# Mechaduino01.net
KiCad netlist of a schematic drawn in EAGLE
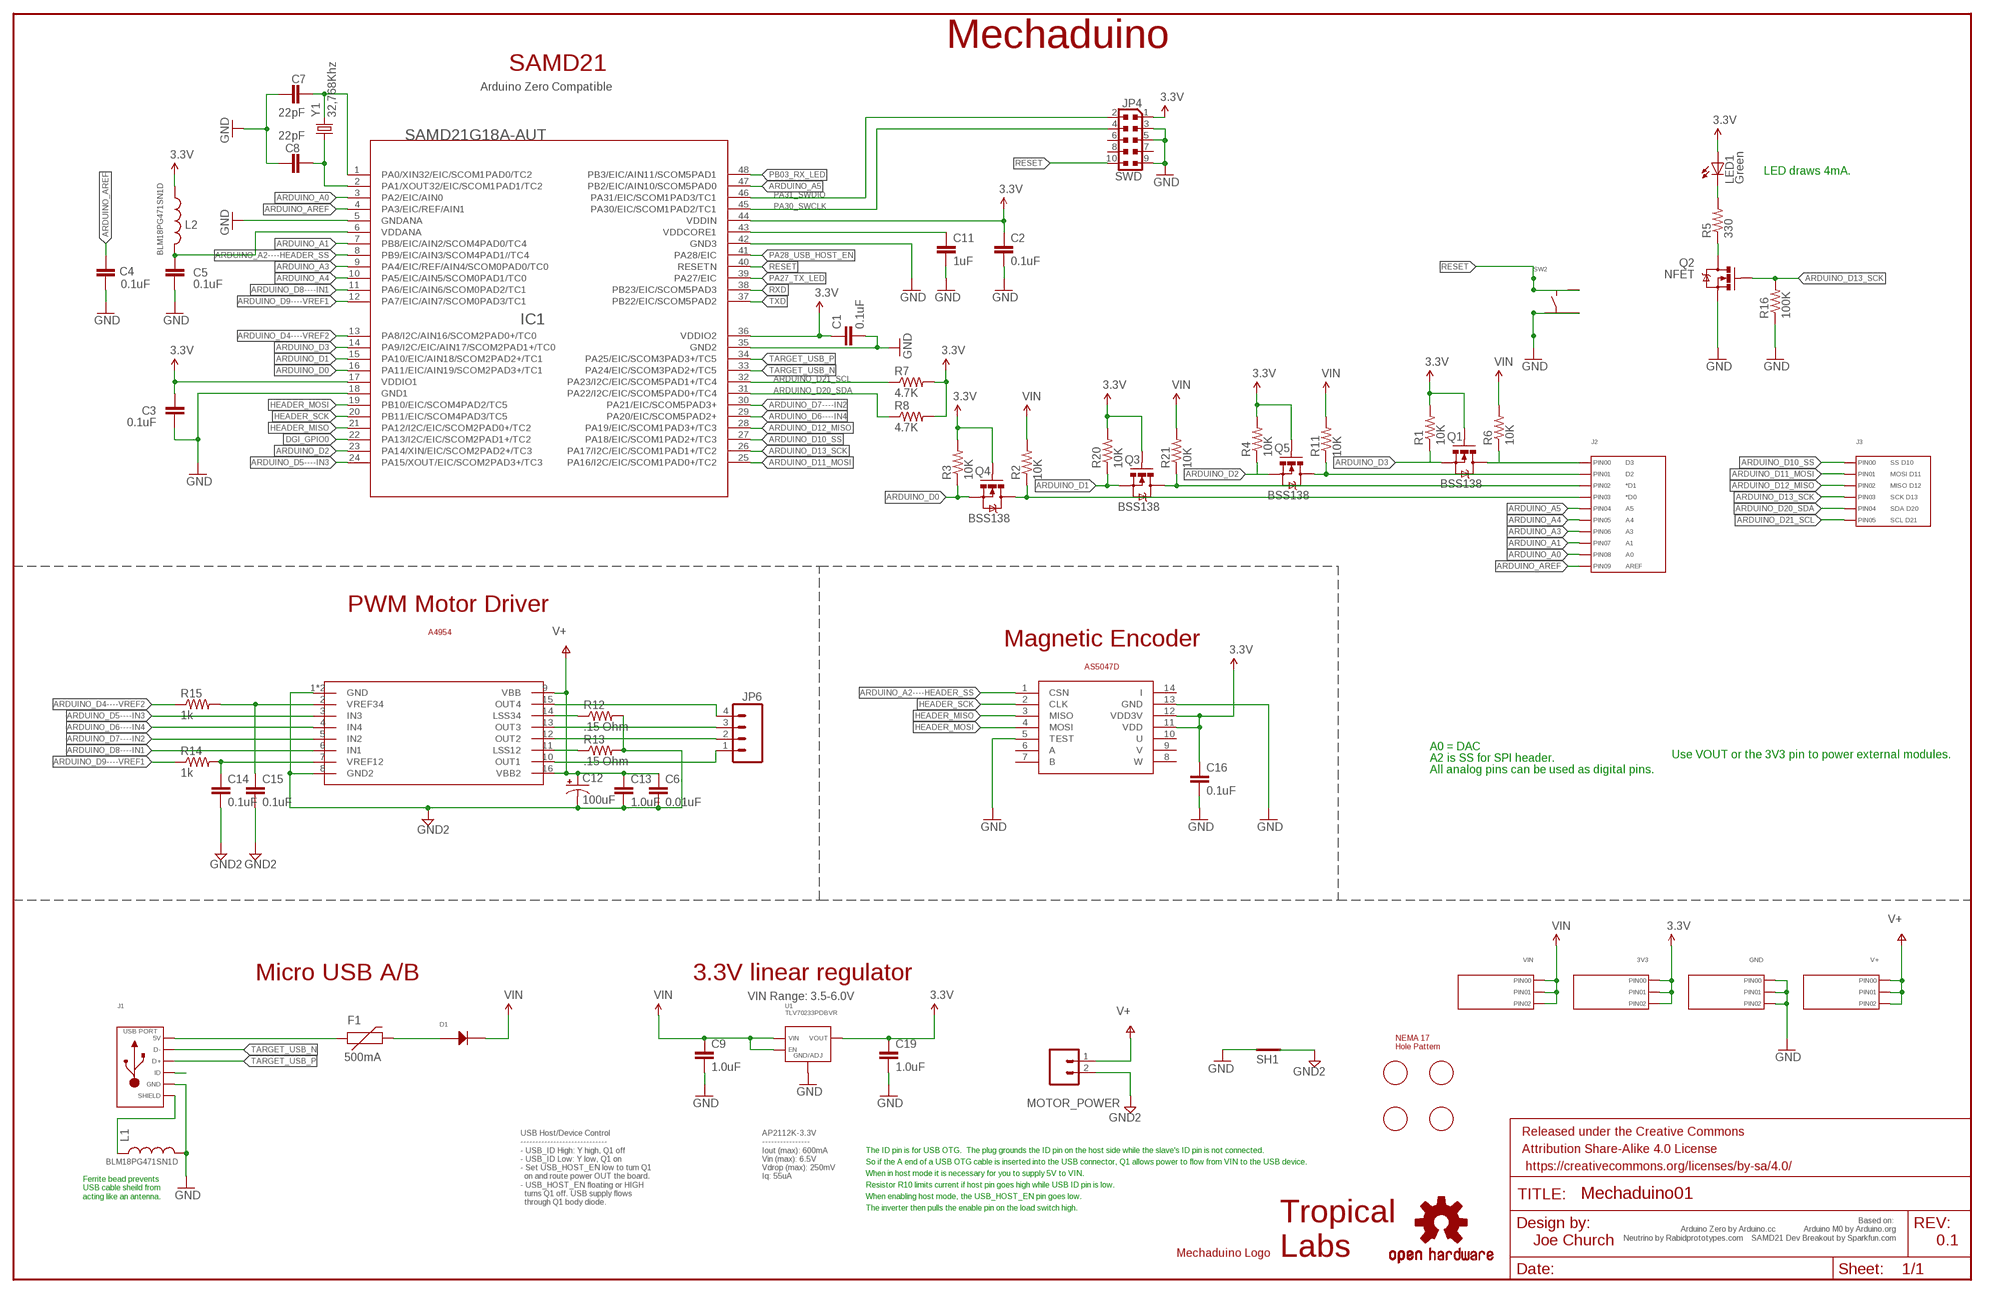
[diagram p0: schematic, sheet 1]

(export (version "E")
  (design (tool "Eeschema 10.0.6"))
  (components
    (comp (ref "3V3")
      (value "HEADER_01X03_PTH_2.54MM")
      (footprint "eagle-import:PTH_2.54MM_01X03")
      (libsource (lib "eagle-import") (part "HEADER_01X03_PTH_2.54MM"))
    )
    (comp (ref "C1")
      (value "0.1uF")
      (footprint "eagle-import:0402-CAP")
      (libsource (lib "eagle-import") (part "CAP0402"))
    )
    (comp (ref "C2")
      (value "0.1uF")
      (footprint "eagle-import:0402-CAP")
      (libsource (lib "eagle-import") (part "CAP0402"))
    )
    (comp (ref "C3")
      (value "0.1uF")
      (footprint "eagle-import:0402-CAP")
      (libsource (lib "eagle-import") (part "CAP0402"))
    )
    (comp (ref "C4")
      (value "0.1uF")
      (footprint "eagle-import:0402-CAP")
      (libsource (lib "eagle-import") (part "CAP0402"))
    )
    (comp (ref "C5")
      (value "0.1uF")
      (footprint "eagle-import:0402-CAP")
      (libsource (lib "eagle-import") (part "CAP0402"))
    )
    (comp (ref "C6")
      (value "0.01uF")
      (footprint "eagle-import:0402-CAP")
      (libsource (lib "eagle-import") (part "CAP0402"))
    )
    (comp (ref "C7")
      (value "22pF")
      (footprint "eagle-import:0402-CAP")
      (libsource (lib "eagle-import") (part "CAP0402"))
    )
    (comp (ref "C8")
      (value "22pF")
      (footprint "eagle-import:0402-CAP")
      (libsource (lib "eagle-import") (part "CAP0402"))
    )
    (comp (ref "C9")
      (value "1.0uF")
      (footprint "eagle-import:0402-CAP")
      (libsource (lib "eagle-import") (part "CAP0402"))
    )
    (comp (ref "C11")
      (value "1uF")
      (footprint "eagle-import:0402-CAP")
      (libsource (lib "eagle-import") (part "CAP0402"))
    )
    (comp (ref "C12")
      (value "100uF")
      (footprint "eagle-import:PANASONIC_D")
      (libsource (lib "eagle-import") (part "CAP_POLD"))
    )
    (comp (ref "C13")
      (value "1.0uF")
      (footprint "eagle-import:0603-CAP")
      (libsource (lib "eagle-import") (part "CAP0603"))
    )
    (comp (ref "C14")
      (value "0.1uF")
      (footprint "eagle-import:0402-CAP")
      (libsource (lib "eagle-import") (part "CAP0402"))
    )
    (comp (ref "C15")
      (value "0.1uF")
      (footprint "eagle-import:0402-CAP")
      (libsource (lib "eagle-import") (part "CAP0402"))
    )
    (comp (ref "C16")
      (value "0.1uF")
      (footprint "eagle-import:0402-CAP")
      (libsource (lib "eagle-import") (part "CAP0402"))
    )
    (comp (ref "C19")
      (value "1.0uF")
      (footprint "eagle-import:0402-CAP")
      (libsource (lib "eagle-import") (part "CAP0402"))
    )
    (comp (ref "D1")
      (value "DIODE_SOD-123")
      (footprint "eagle-import:SOD-123")
      (libsource (lib "eagle-import") (part "DIODE_SOD-123"))
    )
    (comp (ref "F1")
      (value "500mA")
      (footprint "eagle-import:PTC-1206")
      (libsource (lib "eagle-import") (part "PTCSMD"))
    )
    (comp (ref "FRAME1")
      (value "FRAME-LEDGER")
      (footprint "eagle-import:CREATIVE_COMMONS")
      (libsource (lib "eagle-import") (part "FRAME-LEDGER"))
    )
    (comp (ref "GND")
      (value "HEADER_01X03_PTH_2.54MM")
      (footprint "eagle-import:PTH_2.54MM_01X03")
      (libsource (lib "eagle-import") (part "HEADER_01X03_PTH_2.54MM"))
    )
    (comp (ref "IC1")
      (value "SAMD21G18A-AUT")
      (footprint "eagle-import:INTEGRATEDCIRCUITS_TQFP48-7X7")
      (libsource (lib "eagle-import") (part "INTEGRATEDCIRCUITS_1792_SAMD21G18A-AUT"))
    )
    (comp (ref "J1")
      (value "USB_MICRO_RIGHT")
      (footprint "eagle-import:MICROUSB-RIGHT")
      (libsource (lib "eagle-import") (part "USB_MICRO_RIGHT"))
    )
    (comp (ref "J2")
      (value "HEADER_01X10_PTH_2.54MM")
      (footprint "eagle-import:PTH_2.54MM_01X10")
      (fields
        (field (name "LABEL00") "D3")
        (field (name "LABEL01") "D2")
        (field (name "LABEL02") "*D1")
        (field (name "LABEL03") "*D0")
        (field (name "LABEL04") "A5")
        (field (name "LABEL05") "A4")
        (field (name "LABEL06") "A3")
        (field (name "LABEL07") "A1")
        (field (name "LABEL08") "A0")
        (field (name "LABEL09") "AREF")
      )
      (libsource (lib "eagle-import") (part "HEADER_01X10_PTH_2.54MM"))
    )
    (comp (ref "J3")
      (value "HEADER_01X06_PTH_2.54MM")
      (footprint "eagle-import:PTH_2.54MM_01X06")
      (fields
        (field (name "LABEL00") "SS D10")
        (field (name "LABEL01") "MOSI D11")
        (field (name "LABEL02") "MISO D12")
        (field (name "LABEL03") "SCK D13")
        (field (name "LABEL04") "SDA D20")
        (field (name "LABEL05") "SCL D21")
      )
      (libsource (lib "eagle-import") (part "HEADER_01X06_PTH_2.54MM"))
    )
    (comp (ref "JP4")
      (value "SWD")
      (footprint "eagle-import:CONNETTORI_PINHEAD-2X5-P127")
      (libsource (lib "eagle-import") (part "CONNETTORI_0171_PH127-205DF055G00A"))
    )
    (comp (ref "JP6")
      (value "M04PTH")
      (footprint "eagle-import:1X04")
      (libsource (lib "eagle-import") (part "M04PTH"))
    )
    (comp (ref "L1")
      (value "BLM18PG471SN1D")
      (footprint "eagle-import:0603-TDK")
      (libsource (lib "eagle-import") (part "INDUCTOR0603-TDK"))
    )
    (comp (ref "L2")
      (value "BLM18PG471SN1D")
      (footprint "eagle-import:0603-TDK")
      (libsource (lib "eagle-import") (part "INDUCTOR0603-TDK"))
    )
    (comp (ref "LED1")
      (value "Green")
      (footprint "eagle-import:CHIPLED_0805")
      (fields (field (name "PART_NUMBER") "KPT-2012YC"))
      (libsource (lib "eagle-import") (part "0044_KPT-2012YC"))
    )
    (comp (ref "LOGO4")
      (value "OSHW-LOGOL-COPPER")
      (footprint "eagle-import:OSHW-LOGO-L_COPPER")
      (libsource (lib "eagle-import") (part "OSHW-LOGOL-COPPER"))
    )
    (comp (ref "MOTOR_POWER")
      (value "M025MM")
      (footprint "eagle-import:SCREWTERMINAL-5MM-2")
      (libsource (lib "eagle-import") (part "M025MM"))
    )
    (comp (ref "Q1")
      (value "BSS138")
      (footprint "eagle-import:SOT23-3")
      (libsource (lib "eagle-import") (part "MOSFET-NCHANNELSMD"))
    )
    (comp (ref "Q2")
      (value "NFET")
      (footprint "eagle-import:SOT323")
      (libsource (lib "eagle-import") (part "MOSFET-NCHANNEL2N7002PW"))
    )
    (comp (ref "Q3")
      (value "BSS138")
      (footprint "eagle-import:SOT23-3")
      (libsource (lib "eagle-import") (part "MOSFET-NCHANNELSMD"))
    )
    (comp (ref "Q4")
      (value "BSS138")
      (footprint "eagle-import:SOT23-3")
      (libsource (lib "eagle-import") (part "MOSFET-NCHANNELSMD"))
    )
    (comp (ref "Q5")
      (value "BSS138")
      (footprint "eagle-import:SOT23-3")
      (libsource (lib "eagle-import") (part "MOSFET-NCHANNELSMD"))
    )
    (comp (ref "R1")
      (value "10K")
      (footprint "eagle-import:R0402-VISHAY")
      (libsource (lib "eagle-import") (part "R-US_R0402-VISHAY"))
    )
    (comp (ref "R2")
      (value "10K")
      (footprint "eagle-import:R0402-VISHAY")
      (libsource (lib "eagle-import") (part "R-US_R0402-VISHAY"))
    )
    (comp (ref "R3")
      (value "10K")
      (footprint "eagle-import:R0402-VISHAY")
      (libsource (lib "eagle-import") (part "R-US_R0402-VISHAY"))
    )
    (comp (ref "R4")
      (value "10K")
      (footprint "eagle-import:R0402-VISHAY")
      (libsource (lib "eagle-import") (part "R-US_R0402-VISHAY"))
    )
    (comp (ref "R5")
      (value "330")
      (footprint "eagle-import:R0402-VISHAY")
      (libsource (lib "eagle-import") (part "R-US_R0402-VISHAY"))
    )
    (comp (ref "R6")
      (value "10K")
      (footprint "eagle-import:R0402-VISHAY")
      (libsource (lib "eagle-import") (part "R-US_R0402-VISHAY"))
    )
    (comp (ref "R7")
      (value "4.7K")
      (footprint "eagle-import:R0402-VISHAY")
      (libsource (lib "eagle-import") (part "R-US_R0402-VISHAY"))
    )
    (comp (ref "R8")
      (value "4.7K")
      (footprint "eagle-import:R0402-VISHAY")
      (libsource (lib "eagle-import") (part "R-US_R0402-VISHAY"))
    )
    (comp (ref "R11")
      (value "10K")
      (footprint "eagle-import:R0402-VISHAY")
      (libsource (lib "eagle-import") (part "R-US_R0402-VISHAY"))
    )
    (comp (ref "R12")
      (value ".15 Ohm")
      (footprint "eagle-import:R1206")
      (libsource (lib "eagle-import") (part "R-US_R1206"))
    )
    (comp (ref "R13")
      (value ".15 Ohm")
      (footprint "eagle-import:R1206")
      (libsource (lib "eagle-import") (part "R-US_R1206"))
    )
    (comp (ref "R14")
      (value "1k")
      (footprint "eagle-import:R0402-VISHAY")
      (libsource (lib "eagle-import") (part "R-US_R0402-VISHAY"))
    )
    (comp (ref "R15")
      (value "1k")
      (footprint "eagle-import:R0402-VISHAY")
      (libsource (lib "eagle-import") (part "R-US_R0402-VISHAY"))
    )
    (comp (ref "R16")
      (value "100K")
      (footprint "eagle-import:R0402-VISHAY")
      (libsource (lib "eagle-import") (part "R-US_R0402-VISHAY"))
    )
    (comp (ref "R20")
      (value "10K")
      (footprint "eagle-import:R0402-VISHAY")
      (libsource (lib "eagle-import") (part "R-US_R0402-VISHAY"))
    )
    (comp (ref "R21")
      (value "10K")
      (footprint "eagle-import:R0402-VISHAY")
      (libsource (lib "eagle-import") (part "R-US_R0402-VISHAY"))
    )
    (comp (ref "SH1")
      (value "SHORT-HA5")
      (footprint "eagle-import:SHORT_ALL-50")
      (libsource (lib "eagle-import") (part "SHORT-HA5"))
    )
    (comp (ref "SW2")
      (value "TACT_4.2MM")
      (footprint "eagle-import:TACT4.2MM")
      (libsource (lib "eagle-import") (part "TACT_4.2MM"))
    )
    (comp (ref "U$1")
      (value "AVAGO_DRIVERTHERM")
      (footprint "eagle-import:TSSOP16_THERM")
      (libsource (lib "eagle-import") (part "AVAGO_DRIVERTHERM"))
    )
    (comp (ref "U$2")
      (value "NEMA17_HOLE_PATTERNNEW")
      (footprint "eagle-import:NEMA17_HOLE_PATTERN_2")
      (libsource (lib "eagle-import") (part "NEMA17_HOLE_PATTERNNEW"))
    )
    (comp (ref "U$3")
      (value "TROPICAL_LABS_LOGO_1LOGO3")
      (footprint "eagle-import:LOGO3")
      (libsource (lib "eagle-import") (part "TROPICAL_LABS_LOGO_1LOGO3"))
    )
    (comp (ref "U$4")
      (value "AS5047D")
      (footprint "eagle-import:TSSOP14")
      (libsource (lib "eagle-import") (part "AS5047D"))
    )
    (comp (ref "U$5")
      (value "MECHADUINO_LOGO")
      (footprint "eagle-import:MECHADUINO_LOGO")
      (libsource (lib "eagle-import") (part "MECHADUINO_LOGO"))
    )
    (comp (ref "U1")
      (value "TLV70233PDBVR")
      (footprint "eagle-import:SOT-23-5")
      (libsource (lib "eagle-import") (part "TLV70233PDBVR"))
    )
    (comp (ref "V+")
      (value "HEADER_01X03_PTH_2.54MM")
      (footprint "eagle-import:PTH_2.54MM_01X03")
      (libsource (lib "eagle-import") (part "HEADER_01X03_PTH_2.54MM"))
    )
    (comp (ref "VIN")
      (value "HEADER_01X03_PTH_2.54MM")
      (footprint "eagle-import:PTH_2.54MM_01X03")
      (libsource (lib "eagle-import") (part "HEADER_01X03_PTH_2.54MM"))
    )
    (comp (ref "Y1")
      (value "32,768Khz")
      (footprint "eagle-import:CRYSTAL-SMD-2.0X1.2")
      (libsource (lib "eagle-import") (part "CRYSTAL2012"))
    )
  )
  (nets
    (net (code "1") (name "/PA30_SWCLK") (class "Default")
      (node (ref "IC1") (pin "45") (pinfunction "PA30/EIC/SCOM1PAD2/TC1_45") (pintype "bidirectional"))
      (node (ref "JP4") (pin "4") (pinfunction "4_4") (pintype "passive"))
    )
    (net (code "2") (name "/PA31_SWDIO") (class "Default")
      (node (ref "IC1") (pin "46") (pinfunction "PA31/EIC/SCOM1PAD3/TC1_46") (pintype "bidirectional"))
      (node (ref "JP4") (pin "2") (pinfunction "2_2") (pintype "passive"))
    )
    (net (code "3") (name "3.3V") (class "Default")
      (node (ref "3V3") (pin "P$1") (pinfunction "PIN0_P$1") (pintype "bidirectional"))
      (node (ref "3V3") (pin "P$2") (pinfunction "PIN1_P$2") (pintype "bidirectional"))
      (node (ref "3V3") (pin "P$3") (pinfunction "PIN2_P$3") (pintype "bidirectional"))
      (node (ref "C1") (pin "1") (pinfunction "1_1") (pintype "passive"))
      (node (ref "C16") (pin "1") (pinfunction "1_1") (pintype "passive"))
      (node (ref "C19") (pin "1") (pinfunction "1_1") (pintype "passive"))
      (node (ref "C2") (pin "1") (pinfunction "1_1") (pintype "passive"))
      (node (ref "C3") (pin "2") (pinfunction "2_2") (pintype "passive"))
      (node (ref "IC1") (pin "17") (pinfunction "VDDIO1_17") (pintype "power_in"))
      (node (ref "IC1") (pin "36") (pinfunction "VDDIO2_36") (pintype "power_in"))
      (node (ref "IC1") (pin "44") (pinfunction "VDDIN_44") (pintype "power_in"))
      (node (ref "JP4") (pin "1") (pinfunction "1_1") (pintype "passive"))
      (node (ref "L2") (pin "1") (pinfunction "1_1") (pintype "passive"))
      (node (ref "LED1") (pin "A") (pinfunction "A_A") (pintype "passive"))
      (node (ref "Q1") (pin "1") (pinfunction "G_1") (pintype "passive"))
      (node (ref "Q3") (pin "1") (pinfunction "G_1") (pintype "passive"))
      (node (ref "Q4") (pin "1") (pinfunction "G_1") (pintype "passive"))
      (node (ref "Q5") (pin "1") (pinfunction "G_1") (pintype "passive"))
      (node (ref "R1") (pin "2") (pinfunction "2_2") (pintype "passive"))
      (node (ref "R20") (pin "2") (pinfunction "2_2") (pintype "passive"))
      (node (ref "R3") (pin "2") (pinfunction "2_2") (pintype "passive"))
      (node (ref "R4") (pin "2") (pinfunction "2_2") (pintype "passive"))
      (node (ref "R7") (pin "2") (pinfunction "2_2") (pintype "passive"))
      (node (ref "R8") (pin "2") (pinfunction "2_2") (pintype "passive"))
      (node (ref "U$4") (pin "11") (pinfunction "VDD_11") (pintype "bidirectional"))
      (node (ref "U$4") (pin "12") (pinfunction "VDD3V_12") (pintype "bidirectional"))
      (node (ref "U1") (pin "P$5") (pinfunction "VOUT_P$5") (pintype "bidirectional"))
    )
    (net (code "4") (name "ARDUINO_A0") (class "Default")
      (node (ref "IC1") (pin "3") (pinfunction "PA2/EIC/AIN0_3") (pintype "bidirectional"))
      (node (ref "J2") (pin "P$9") (pinfunction "PIN8_P$9") (pintype "bidirectional"))
    )
    (net (code "5") (name "ARDUINO_A1") (class "Default")
      (node (ref "IC1") (pin "7") (pinfunction "PB8/EIC/AIN2/SCOM4PAD0/TC4_7") (pintype "bidirectional"))
      (node (ref "J2") (pin "P$8") (pinfunction "PIN7_P$8") (pintype "bidirectional"))
    )
    (net (code "6") (name "ARDUINO_A2----HEADER_SS") (class "Default")
      (node (ref "IC1") (pin "8") (pinfunction "PB9/EIC/AIN3/SCOM4PAD1//TC4_8") (pintype "bidirectional"))
      (node (ref "U$4") (pin "1") (pinfunction "CSN_1") (pintype "bidirectional"))
    )
    (net (code "7") (name "ARDUINO_A3") (class "Default")
      (node (ref "IC1") (pin "9") (pinfunction "PA4/EIC/REF/AIN4/SCOM0PAD0/TC0_9") (pintype "bidirectional"))
      (node (ref "J2") (pin "P$7") (pinfunction "PIN6_P$7") (pintype "bidirectional"))
    )
    (net (code "8") (name "ARDUINO_A4") (class "Default")
      (node (ref "IC1") (pin "10") (pinfunction "PA5/EIC/AIN5/SCOM0PAD1/TC0_10") (pintype "bidirectional"))
      (node (ref "J2") (pin "P$6") (pinfunction "PIN5_P$6") (pintype "bidirectional"))
    )
    (net (code "9") (name "ARDUINO_A5") (class "Default")
      (node (ref "IC1") (pin "47") (pinfunction "PB2/EIC/AIN10/SCOM5PAD0_47") (pintype "bidirectional"))
      (node (ref "J2") (pin "P$5") (pinfunction "PIN4_P$5") (pintype "bidirectional"))
    )
    (net (code "10") (name "ARDUINO_AREF") (class "Default")
      (node (ref "C4") (pin "1") (pinfunction "1_1") (pintype "passive"))
      (node (ref "IC1") (pin "4") (pinfunction "PA3/EIC/REF/AIN1_4") (pintype "bidirectional"))
      (node (ref "J2") (pin "P$10") (pinfunction "PIN9_P$10") (pintype "bidirectional"))
    )
    (net (code "11") (name "ARDUINO_D0") (class "Default")
      (node (ref "IC1") (pin "16") (pinfunction "PA11/EIC/AIN19/SCOM2PAD3+/TC1_16") (pintype "bidirectional"))
      (node (ref "Q4") (pin "2") (pinfunction "S_2") (pintype "passive"))
      (node (ref "R3") (pin "1") (pinfunction "1_1") (pintype "passive"))
    )
    (net (code "12") (name "ARDUINO_D1") (class "Default")
      (node (ref "IC1") (pin "15") (pinfunction "PA10/EIC/AIN18/SCOM2PAD2+/TC1_15") (pintype "bidirectional"))
      (node (ref "Q3") (pin "2") (pinfunction "S_2") (pintype "passive"))
      (node (ref "R20") (pin "1") (pinfunction "1_1") (pintype "passive"))
    )
    (net (code "13") (name "ARDUINO_D2") (class "Default")
      (node (ref "IC1") (pin "23") (pinfunction "PA14/XIN/EIC/SCOM2PAD2+/TC3_23") (pintype "bidirectional"))
      (node (ref "Q5") (pin "2") (pinfunction "S_2") (pintype "passive"))
      (node (ref "R4") (pin "1") (pinfunction "1_1") (pintype "passive"))
    )
    (net (code "14") (name "ARDUINO_D3") (class "Default")
      (node (ref "IC1") (pin "14") (pinfunction "PA9/I2C/EIC/AIN17/SCOM2PAD1+/TC0_14") (pintype "bidirectional"))
      (node (ref "Q1") (pin "2") (pinfunction "S_2") (pintype "passive"))
      (node (ref "R1") (pin "1") (pinfunction "1_1") (pintype "passive"))
    )
    (net (code "15") (name "ARDUINO_D4----VREF2") (class "Default")
      (node (ref "IC1") (pin "13") (pinfunction "PA8/I2C/AIN16/SCOM2PAD0+/TC0_13") (pintype "bidirectional"))
      (node (ref "R15") (pin "1") (pinfunction "1_1") (pintype "passive"))
    )
    (net (code "16") (name "ARDUINO_D5----IN3") (class "Default")
      (node (ref "IC1") (pin "24") (pinfunction "PA15/XOUT/EIC/SCOM2PAD3+/TC3_24") (pintype "bidirectional"))
      (node (ref "U$1") (pin "3") (pinfunction "IN3_3") (pintype "bidirectional"))
    )
    (net (code "17") (name "ARDUINO_D6----IN4") (class "Default")
      (node (ref "IC1") (pin "29") (pinfunction "PA20/EIC/SCOM5PAD2+_29") (pintype "bidirectional"))
      (node (ref "U$1") (pin "4") (pinfunction "IN4_4") (pintype "bidirectional"))
    )
    (net (code "18") (name "ARDUINO_D7----IN2") (class "Default")
      (node (ref "IC1") (pin "30") (pinfunction "PA21/EIC/SCOM5PAD3+_30") (pintype "bidirectional"))
      (node (ref "U$1") (pin "5") (pinfunction "IN2_5") (pintype "bidirectional"))
    )
    (net (code "19") (name "ARDUINO_D8----IN1") (class "Default")
      (node (ref "IC1") (pin "11") (pinfunction "PA6/EIC/AIN6/SCOM0PAD2/TC1_11") (pintype "bidirectional"))
      (node (ref "U$1") (pin "6") (pinfunction "IN1_6") (pintype "bidirectional"))
    )
    (net (code "20") (name "ARDUINO_D9----VREF1") (class "Default")
      (node (ref "IC1") (pin "12") (pinfunction "PA7/EIC/AIN7/SCOM0PAD3/TC1_12") (pintype "bidirectional"))
      (node (ref "R14") (pin "1") (pinfunction "1_1") (pintype "passive"))
    )
    (net (code "21") (name "ARDUINO_D10_SS") (class "Default")
      (node (ref "IC1") (pin "27") (pinfunction "PA18/EIC/SCOM1PAD2+/TC3_27") (pintype "bidirectional"))
      (node (ref "J3") (pin "P$1") (pinfunction "PIN0_P$1") (pintype "bidirectional"))
    )
    (net (code "22") (name "ARDUINO_D11_MOSI") (class "Default")
      (node (ref "IC1") (pin "25") (pinfunction "PA16/I2C/EIC/SCOM1PAD0+/TC2_25") (pintype "bidirectional"))
      (node (ref "J3") (pin "P$2") (pinfunction "PIN1_P$2") (pintype "bidirectional"))
    )
    (net (code "23") (name "ARDUINO_D12_MISO") (class "Default")
      (node (ref "IC1") (pin "28") (pinfunction "PA19/EIC/SCOM1PAD3+/TC3_28") (pintype "bidirectional"))
      (node (ref "J3") (pin "P$3") (pinfunction "PIN2_P$3") (pintype "bidirectional"))
    )
    (net (code "24") (name "ARDUINO_D13_SCK") (class "Default")
      (node (ref "IC1") (pin "26") (pinfunction "PA17/I2C/EIC/SCOM1PAD1+/TC2_26") (pintype "bidirectional"))
      (node (ref "J3") (pin "P$4") (pinfunction "PIN3_P$4") (pintype "bidirectional"))
      (node (ref "Q2") (pin "1") (pinfunction "G_1") (pintype "passive"))
      (node (ref "R16") (pin "2") (pinfunction "2_2") (pintype "passive"))
    )
    (net (code "25") (name "ARDUINO_D20_SDA") (class "Default")
      (node (ref "IC1") (pin "31") (pinfunction "PA22/I2C/EIC/SCOM5PAD0+/TC4_31") (pintype "bidirectional"))
      (node (ref "J3") (pin "P$5") (pinfunction "PIN4_P$5") (pintype "bidirectional"))
      (node (ref "R8") (pin "1") (pinfunction "1_1") (pintype "passive"))
    )
    (net (code "26") (name "ARDUINO_D21_SCL") (class "Default")
      (node (ref "IC1") (pin "32") (pinfunction "PA23/I2C/EIC/SCOM5PAD1+/TC4_32") (pintype "bidirectional"))
      (node (ref "J3") (pin "P$6") (pinfunction "PIN5_P$6") (pintype "bidirectional"))
      (node (ref "R7") (pin "1") (pinfunction "1_1") (pintype "passive"))
    )
    (net (code "27") (name "DGI_GPIO0") (class "Default")
      (node (ref "IC1") (pin "22") (pinfunction "PA13/I2C/EIC/SCOM2PAD1+/TC2_22") (pintype "bidirectional"))
    )
    (net (code "28") (name "GND") (class "Default")
      (node (ref "C1") (pin "2") (pinfunction "2_2") (pintype "passive"))
      (node (ref "C11") (pin "2") (pinfunction "2_2") (pintype "passive"))
      (node (ref "C16") (pin "2") (pinfunction "2_2") (pintype "passive"))
      (node (ref "C19") (pin "2") (pinfunction "2_2") (pintype "passive"))
      (node (ref "C2") (pin "2") (pinfunction "2_2") (pintype "passive"))
      (node (ref "C3") (pin "1") (pinfunction "1_1") (pintype "passive"))
      (node (ref "C4") (pin "2") (pinfunction "2_2") (pintype "passive"))
      (node (ref "C5") (pin "2") (pinfunction "2_2") (pintype "passive"))
      (node (ref "C7") (pin "1") (pinfunction "1_1") (pintype "passive"))
      (node (ref "C8") (pin "1") (pinfunction "1_1") (pintype "passive"))
      (node (ref "C9") (pin "2") (pinfunction "2_2") (pintype "passive"))
      (node (ref "GND") (pin "P$1") (pinfunction "PIN0_P$1") (pintype "bidirectional"))
      (node (ref "GND") (pin "P$2") (pinfunction "PIN1_P$2") (pintype "bidirectional"))
      (node (ref "GND") (pin "P$3") (pinfunction "PIN2_P$3") (pintype "bidirectional"))
      (node (ref "IC1") (pin "18") (pinfunction "GND1_18") (pintype "power_in"))
      (node (ref "IC1") (pin "35") (pinfunction "GND2_35") (pintype "power_in"))
      (node (ref "IC1") (pin "42") (pinfunction "GND3_42") (pintype "power_in"))
      (node (ref "IC1") (pin "5") (pinfunction "GNDANA_5") (pintype "power_in"))
      (node (ref "J1") (pin "5") (pinfunction "GND_5") (pintype "power_in"))
      (node (ref "JP4") (pin "3") (pinfunction "3_3") (pintype "passive"))
      (node (ref "JP4") (pin "5") (pinfunction "5_5") (pintype "passive"))
      (node (ref "JP4") (pin "9") (pinfunction "9_9") (pintype "passive"))
      (node (ref "L1") (pin "2") (pinfunction "2_2") (pintype "passive"))
      (node (ref "Q2") (pin "2") (pinfunction "S_2") (pintype "passive"))
      (node (ref "R16") (pin "1") (pinfunction "1_1") (pintype "passive"))
      (node (ref "SH1") (pin "2") (pinfunction "P$2_2") (pintype "bidirectional"))
      (node (ref "SW2") (pin "P$3") (pinfunction "P$3_P$3") (pintype "bidirectional"))
      (node (ref "SW2") (pin "P$4") (pinfunction "P$4_P$4") (pintype "bidirectional"))
      (node (ref "U$4") (pin "13") (pinfunction "GND_13") (pintype "bidirectional"))
      (node (ref "U$4") (pin "5") (pinfunction "TEST_5") (pintype "bidirectional"))
      (node (ref "U1") (pin "P$2") (pinfunction "GND/ADJ_P$2") (pintype "bidirectional"))
    )
    (net (code "29") (name "GND2") (class "Default")
      (node (ref "C12") (pin "-") (pinfunction "-_-") (pintype "passive"))
      (node (ref "C13") (pin "2") (pinfunction "2_2") (pintype "passive"))
      (node (ref "C14") (pin "2") (pinfunction "2_2") (pintype "passive"))
      (node (ref "C15") (pin "2") (pinfunction "2_2") (pintype "passive"))
      (node (ref "C6") (pin "2") (pinfunction "2_2") (pintype "passive"))
      (node (ref "MOTOR_POWER") (pin "2") (pinfunction "2_2") (pintype "passive"))
      (node (ref "R12") (pin "2") (pinfunction "2_2") (pintype "passive"))
      (node (ref "R13") (pin "2") (pinfunction "2_2") (pintype "passive"))
      (node (ref "SH1") (pin "1") (pinfunction "P$1_1") (pintype "bidirectional"))
      (node (ref "U$1") (pin "1") (pinfunction "GND_1") (pintype "bidirectional"))
      (node (ref "U$1") (pin "8") (pinfunction "GND2_8") (pintype "bidirectional"))
      (node (ref "U$1") (pin "P$1") (pinfunction "GND_P$1") (pintype "bidirectional"))
    )
    (net (code "30") (name "HEADER_MISO") (class "Default")
      (node (ref "IC1") (pin "21") (pinfunction "PA12/I2C/EIC/SCOM2PAD0+/TC2_21") (pintype "bidirectional"))
      (node (ref "U$4") (pin "3") (pinfunction "MISO_3") (pintype "bidirectional"))
    )
    (net (code "31") (name "HEADER_MOSI") (class "Default")
      (node (ref "IC1") (pin "19") (pinfunction "PB10/EIC/SCOM4PAD2/TC5_19") (pintype "bidirectional"))
      (node (ref "U$4") (pin "4") (pinfunction "MOSI_4") (pintype "bidirectional"))
    )
    (net (code "32") (name "HEADER_SCK") (class "Default")
      (node (ref "IC1") (pin "20") (pinfunction "PB11/EIC/SCOM4PAD3/TC5_20") (pintype "bidirectional"))
      (node (ref "U$4") (pin "2") (pinfunction "CLK_2") (pintype "bidirectional"))
    )
    (net (code "33") (name "Net-(D1-PadANODE)") (class "Default")
      (node (ref "D1") (pin "ANODE") (pinfunction "ANODE_ANODE") (pintype "bidirectional"))
      (node (ref "F1") (pin "2") (pinfunction "2_2") (pintype "bidirectional"))
    )
    (net (code "34") (name "Net-(IC1-PA0{slash}XIN32{slash}EIC{slash}SCOM1PAD0{slash}TC2)") (class "Default")
      (node (ref "C7") (pin "2") (pinfunction "2_2") (pintype "passive"))
      (node (ref "IC1") (pin "1") (pinfunction "PA0/XIN32/EIC/SCOM1PAD0/TC2_1") (pintype "bidirectional"))
      (node (ref "Y1") (pin "2") (pinfunction "2_2") (pintype "passive"))
    )
    (net (code "35") (name "Net-(IC1-PA1{slash}XOUT32{slash}EIC{slash}SCOM1PAD1{slash}TC2)") (class "Default")
      (node (ref "C8") (pin "2") (pinfunction "2_2") (pintype "passive"))
      (node (ref "IC1") (pin "2") (pinfunction "PA1/XOUT32/EIC/SCOM1PAD1/TC2_2") (pintype "bidirectional"))
      (node (ref "Y1") (pin "1") (pinfunction "1_1") (pintype "passive"))
    )
    (net (code "36") (name "Net-(IC1-VDDANA)") (class "Default")
      (node (ref "C5") (pin "1") (pinfunction "1_1") (pintype "passive"))
      (node (ref "IC1") (pin "6") (pinfunction "VDDANA_6") (pintype "power_in"))
      (node (ref "L2") (pin "2") (pinfunction "2_2") (pintype "passive"))
    )
    (net (code "37") (name "Net-(IC1-VDDCORE1)") (class "Default")
      (node (ref "C11") (pin "1") (pinfunction "1_1") (pintype "passive"))
      (node (ref "IC1") (pin "43") (pinfunction "VDDCORE1_43") (pintype "input"))
    )
    (net (code "38") (name "Net-(J1-5V)") (class "Default")
      (node (ref "F1") (pin "1") (pinfunction "1_1") (pintype "bidirectional"))
      (node (ref "J1") (pin "1") (pinfunction "5V_1") (pintype "power_in"))
    )
    (net (code "39") (name "Net-(J1-SLD-PadS1)") (class "Default")
      (node (ref "J1") (pin "S1") (pinfunction "SLD_S1") (pintype "power_in"))
      (node (ref "J1") (pin "S2") (pinfunction "SLD_S2") (pintype "power_in"))
      (node (ref "J1") (pin "S3") (pinfunction "SLD_S3") (pintype "power_in"))
      (node (ref "J1") (pin "S4") (pinfunction "SLD_S4") (pintype "power_in"))
      (node (ref "J1") (pin "S5") (pinfunction "SLD_S5") (pintype "power_in"))
      (node (ref "J1") (pin "S6") (pinfunction "SLD_S6") (pintype "power_in"))
      (node (ref "J1") (pin "S7") (pinfunction "SLD_S7") (pintype "power_in"))
      (node (ref "J1") (pin "S8") (pinfunction "SLD_S8") (pintype "power_in"))
      (node (ref "L1") (pin "1") (pinfunction "1_1") (pintype "passive"))
    )
    (net (code "40") (name "Net-(J2-PIN0)") (class "Default")
      (node (ref "J2") (pin "P$1") (pinfunction "PIN0_P$1") (pintype "bidirectional"))
      (node (ref "Q1") (pin "3") (pinfunction "D_3") (pintype "passive"))
      (node (ref "R6") (pin "1") (pinfunction "1_1") (pintype "passive"))
    )
    (net (code "41") (name "Net-(J2-PIN1)") (class "Default")
      (node (ref "J2") (pin "P$2") (pinfunction "PIN1_P$2") (pintype "bidirectional"))
      (node (ref "Q5") (pin "3") (pinfunction "D_3") (pintype "passive"))
      (node (ref "R11") (pin "1") (pinfunction "1_1") (pintype "passive"))
    )
    (net (code "42") (name "Net-(J2-PIN2)") (class "Default")
      (node (ref "J2") (pin "P$3") (pinfunction "PIN2_P$3") (pintype "bidirectional"))
      (node (ref "Q3") (pin "3") (pinfunction "D_3") (pintype "passive"))
      (node (ref "R21") (pin "1") (pinfunction "1_1") (pintype "passive"))
    )
    (net (code "43") (name "Net-(J2-PIN3)") (class "Default")
      (node (ref "J2") (pin "P$4") (pinfunction "PIN3_P$4") (pintype "bidirectional"))
      (node (ref "Q4") (pin "3") (pinfunction "D_3") (pintype "passive"))
      (node (ref "R2") (pin "1") (pinfunction "1_1") (pintype "passive"))
    )
    (net (code "44") (name "Net-(LED1-PadC)") (class "Default")
      (node (ref "LED1") (pin "C") (pinfunction "C_C") (pintype "passive"))
      (node (ref "R5") (pin "2") (pinfunction "2_2") (pintype "passive"))
    )
    (net (code "45") (name "Net-(Q2-D)") (class "Default")
      (node (ref "Q2") (pin "3") (pinfunction "D_3") (pintype "passive"))
      (node (ref "R5") (pin "1") (pinfunction "1_1") (pintype "passive"))
    )
    (net (code "46") (name "Net-(U$1-LSS12)") (class "Default")
      (node (ref "R13") (pin "1") (pinfunction "1_1") (pintype "passive"))
      (node (ref "U$1") (pin "11") (pinfunction "LSS12_11") (pintype "bidirectional"))
    )
    (net (code "47") (name "Net-(U$1-LSS34)") (class "Default")
      (node (ref "R12") (pin "1") (pinfunction "1_1") (pintype "passive"))
      (node (ref "U$1") (pin "14") (pinfunction "LSS34_14") (pintype "bidirectional"))
    )
    (net (code "48") (name "Net-(U$1-OUT1)") (class "Default")
      (node (ref "JP6") (pin "1") (pinfunction "1_1") (pintype "passive"))
      (node (ref "U$1") (pin "10") (pinfunction "OUT1_10") (pintype "bidirectional"))
    )
    (net (code "49") (name "Net-(U$1-OUT2)") (class "Default")
      (node (ref "JP6") (pin "2") (pinfunction "2_2") (pintype "passive"))
      (node (ref "U$1") (pin "12") (pinfunction "OUT2_12") (pintype "bidirectional"))
    )
    (net (code "50") (name "Net-(U$1-OUT3)") (class "Default")
      (node (ref "JP6") (pin "3") (pinfunction "3_3") (pintype "passive"))
      (node (ref "U$1") (pin "13") (pinfunction "OUT3_13") (pintype "bidirectional"))
    )
    (net (code "51") (name "Net-(U$1-OUT4)") (class "Default")
      (node (ref "JP6") (pin "4") (pinfunction "4_4") (pintype "passive"))
      (node (ref "U$1") (pin "15") (pinfunction "OUT4_15") (pintype "bidirectional"))
    )
    (net (code "52") (name "Net-(U$1-VREF12)") (class "Default")
      (node (ref "C14") (pin "1") (pinfunction "1_1") (pintype "passive"))
      (node (ref "R14") (pin "2") (pinfunction "2_2") (pintype "passive"))
      (node (ref "U$1") (pin "7") (pinfunction "VREF12_7") (pintype "bidirectional"))
    )
    (net (code "53") (name "Net-(U$1-VREF34)") (class "Default")
      (node (ref "C15") (pin "1") (pinfunction "1_1") (pintype "passive"))
      (node (ref "R15") (pin "2") (pinfunction "2_2") (pintype "passive"))
      (node (ref "U$1") (pin "2") (pinfunction "VREF34_2") (pintype "bidirectional"))
    )
    (net (code "54") (name "PA27_TX_LED") (class "Default")
      (node (ref "IC1") (pin "39") (pinfunction "PA27/EIC_39") (pintype "bidirectional"))
    )
    (net (code "55") (name "PA28_USB_HOST_EN") (class "Default")
      (node (ref "IC1") (pin "41") (pinfunction "PA28/EIC_41") (pintype "bidirectional"))
    )
    (net (code "56") (name "PB03_RX_LED") (class "Default")
      (node (ref "IC1") (pin "48") (pinfunction "PB3/EIC/AIN11/SCOM5PAD1_48") (pintype "bidirectional"))
    )
    (net (code "57") (name "RESET") (class "Default")
      (node (ref "IC1") (pin "40") (pinfunction "RESETN_40") (pintype "bidirectional"))
      (node (ref "JP4") (pin "10") (pinfunction "10_10") (pintype "passive"))
      (node (ref "SW2") (pin "P$1") (pinfunction "P$1_P$1") (pintype "bidirectional"))
      (node (ref "SW2") (pin "P$2") (pinfunction "P$2_P$2") (pintype "bidirectional"))
    )
    (net (code "58") (name "RXD") (class "Default")
      (node (ref "IC1") (pin "38") (pinfunction "PB23/EIC/SCOM5PAD3_38") (pintype "bidirectional"))
    )
    (net (code "59") (name "TARGET_USB_N") (class "Default")
      (node (ref "IC1") (pin "33") (pinfunction "PA24/EIC/SCOM3PAD2+/TC5_33") (pintype "bidirectional"))
      (node (ref "J1") (pin "2") (pinfunction "D-_2") (pintype "bidirectional"))
    )
    (net (code "60") (name "TARGET_USB_P") (class "Default")
      (node (ref "IC1") (pin "34") (pinfunction "PA25/EIC/SCOM3PAD3+/TC5_34") (pintype "bidirectional"))
      (node (ref "J1") (pin "3") (pinfunction "D+_3") (pintype "bidirectional"))
    )
    (net (code "61") (name "TXD") (class "Default")
      (node (ref "IC1") (pin "37") (pinfunction "PB22/EIC/SCOM5PAD2_37") (pintype "bidirectional"))
    )
    (net (code "62") (name "V+") (class "Default")
      (node (ref "C12") (pin "+") (pinfunction "+_+") (pintype "passive"))
      (node (ref "C13") (pin "1") (pinfunction "1_1") (pintype "passive"))
      (node (ref "C6") (pin "1") (pinfunction "1_1") (pintype "passive"))
      (node (ref "MOTOR_POWER") (pin "1") (pinfunction "1_1") (pintype "passive"))
      (node (ref "U$1") (pin "16") (pinfunction "VBB2_16") (pintype "bidirectional"))
      (node (ref "U$1") (pin "9") (pinfunction "VBB_9") (pintype "bidirectional"))
      (node (ref "V+") (pin "P$1") (pinfunction "PIN0_P$1") (pintype "bidirectional"))
      (node (ref "V+") (pin "P$2") (pinfunction "PIN1_P$2") (pintype "bidirectional"))
      (node (ref "V+") (pin "P$3") (pinfunction "PIN2_P$3") (pintype "bidirectional"))
    )
    (net (code "63") (name "VIN") (class "Default")
      (node (ref "C9") (pin "1") (pinfunction "1_1") (pintype "passive"))
      (node (ref "D1") (pin "CATHODE") (pinfunction "CATHODE_CATHODE") (pintype "bidirectional"))
      (node (ref "R11") (pin "2") (pinfunction "2_2") (pintype "passive"))
      (node (ref "R2") (pin "2") (pinfunction "2_2") (pintype "passive"))
      (node (ref "R21") (pin "2") (pinfunction "2_2") (pintype "passive"))
      (node (ref "R6") (pin "2") (pinfunction "2_2") (pintype "passive"))
      (node (ref "U1") (pin "P$1") (pinfunction "VIN_P$1") (pintype "bidirectional"))
      (node (ref "U1") (pin "P$3") (pinfunction "EN_P$3") (pintype "bidirectional"))
      (node (ref "VIN") (pin "P$1") (pinfunction "PIN0_P$1") (pintype "bidirectional"))
      (node (ref "VIN") (pin "P$2") (pinfunction "PIN1_P$2") (pintype "bidirectional"))
      (node (ref "VIN") (pin "P$3") (pinfunction "PIN2_P$3") (pintype "bidirectional"))
    )
    (net (code "64") (name "unconnected-(J1-ID-Pad4)") (class "Default")
      (node (ref "J1") (pin "4") (pinfunction "ID_4") (pintype "bidirectional"))
    )
    (net (code "65") (name "unconnected-(JP4-Pad6)") (class "Default")
      (node (ref "JP4") (pin "6") (pinfunction "6_6") (pintype "passive"))
    )
    (net (code "66") (name "unconnected-(JP4-Pad7)") (class "Default")
      (node (ref "JP4") (pin "7") (pinfunction "7_7") (pintype "passive"))
    )
    (net (code "67") (name "unconnected-(JP4-Pad8)") (class "Default")
      (node (ref "JP4") (pin "8") (pinfunction "8_8") (pintype "passive"))
    )
    (net (code "68") (name "unconnected-(U$4-A-Pad6)") (class "Default")
      (node (ref "U$4") (pin "6") (pinfunction "A_6") (pintype "bidirectional"))
    )
    (net (code "69") (name "unconnected-(U$4-B-Pad7)") (class "Default")
      (node (ref "U$4") (pin "7") (pinfunction "B_7") (pintype "bidirectional"))
    )
    (net (code "70") (name "unconnected-(U$4-I-Pad14)") (class "Default")
      (node (ref "U$4") (pin "14") (pinfunction "I_14") (pintype "bidirectional"))
    )
    (net (code "71") (name "unconnected-(U$4-U-Pad10)") (class "Default")
      (node (ref "U$4") (pin "10") (pinfunction "U_10") (pintype "bidirectional"))
    )
    (net (code "72") (name "unconnected-(U$4-V-Pad9)") (class "Default")
      (node (ref "U$4") (pin "9") (pinfunction "V_9") (pintype "bidirectional"))
    )
    (net (code "73") (name "unconnected-(U$4-W-Pad8)") (class "Default")
      (node (ref "U$4") (pin "8") (pinfunction "W_8") (pintype "bidirectional"))
    )
  )
)
